# CPU_JTAG_Power_PLL.net
KiCad netlist of a schematic drawn in Altium Designer
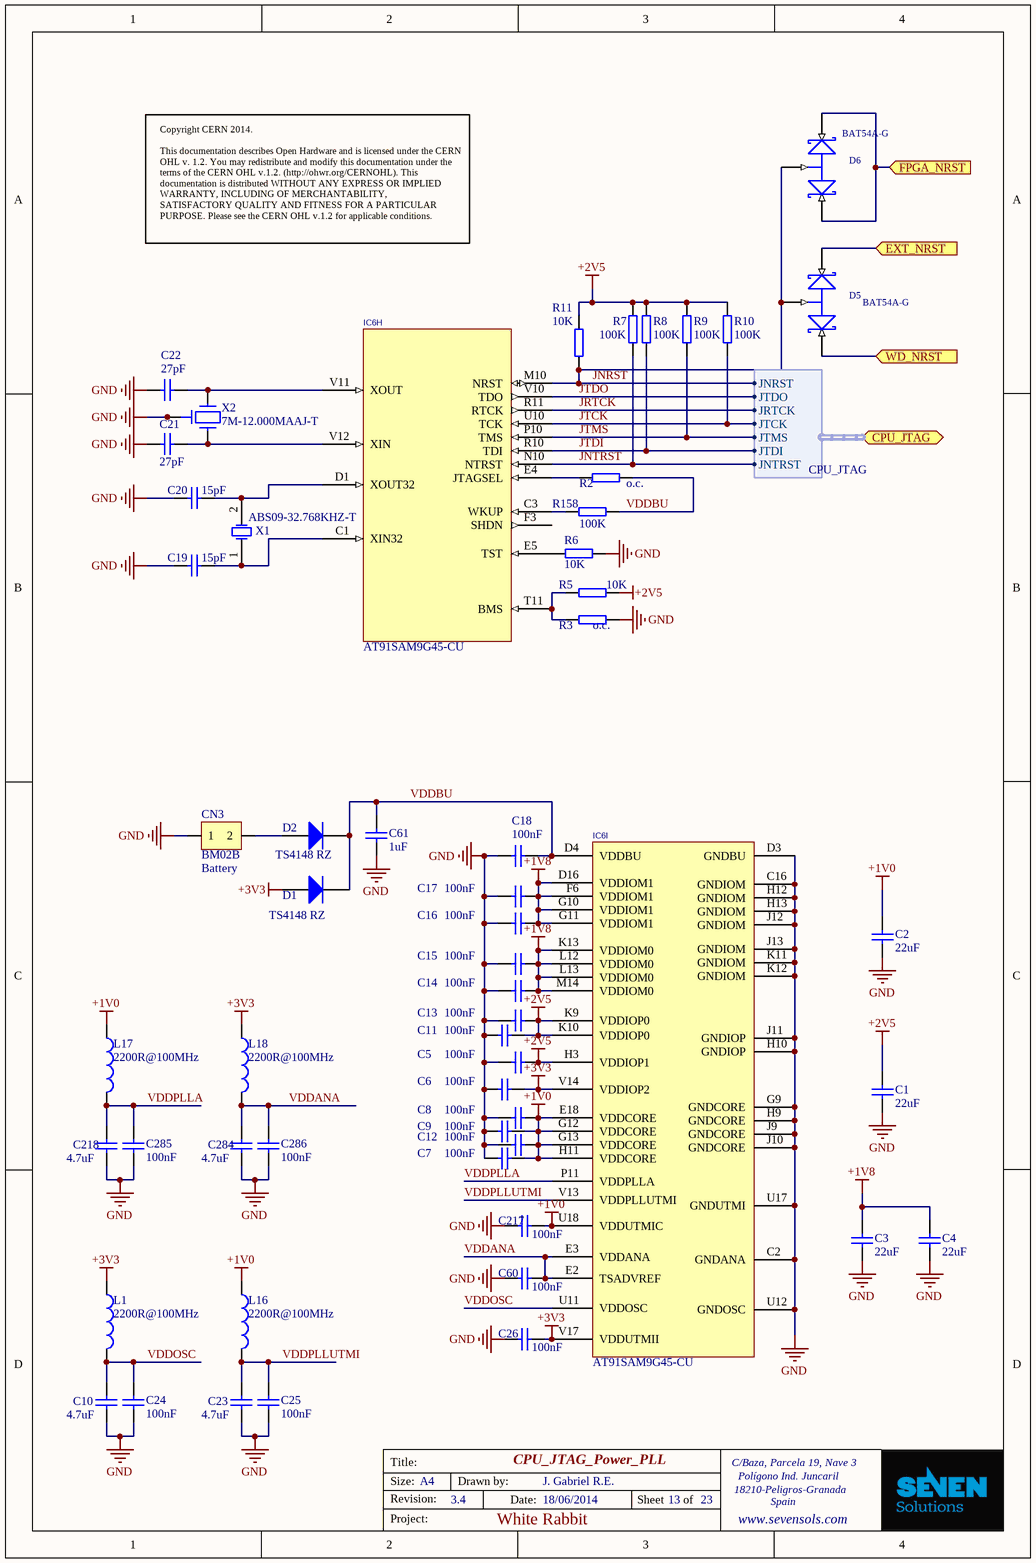
[diagram p0: CPU_JTAG_Power_PLL.SchDoc]

(export (version "E")
  (design (tool "Eeschema 10.0.6"))
  (components
    (comp (ref "C1")
      (value "22uF")
      (footprint "CC2012-0805")
      (description "Capacitor")
      (fields
        (field (name "TOLERANCE") "±20%")
        (field (name "VOLTAGE") "6.3V")
        (field (name "PUBLISHER") "Altium Limited")
      )
      (libsource (lib "wr_switch") (part "Cap"))
    )
    (comp (ref "C2")
      (value "22uF")
      (footprint "CC2012-0805")
      (description "Capacitor")
      (fields
        (field (name "TOLERANCE") "±20%")
        (field (name "VOLTAGE") "6.3V")
        (field (name "PUBLISHER") "Altium Limited")
      )
      (libsource (lib "wr_switch") (part "Cap"))
    )
    (comp (ref "C3")
      (value "22uF")
      (footprint "CC2012-0805")
      (description "Capacitor")
      (fields
        (field (name "TOLERANCE") "±20%")
        (field (name "VOLTAGE") "6.3V")
        (field (name "PUBLISHER") "Altium Limited")
      )
      (libsource (lib "wr_switch") (part "Cap"))
    )
    (comp (ref "C4")
      (value "22uF")
      (footprint "CC2012-0805")
      (description "Capacitor")
      (fields
        (field (name "TOLERANCE") "±20%")
        (field (name "VOLTAGE") "6.3V")
        (field (name "PUBLISHER") "Altium Limited")
      )
      (libsource (lib "wr_switch") (part "Cap"))
    )
    (comp (ref "C5")
      (value "100nF")
      (footprint "CC1005-0402")
      (description "Capacitor")
      (fields
        (field (name "TOLERANCE") "±10%")
        (field (name "VOLTAGE") "16V")
        (field (name "PUBLISHER") "Altium Limited")
      )
      (libsource (lib "wr_switch") (part "Cap"))
    )
    (comp (ref "C6")
      (value "100nF")
      (footprint "CC1005-0402")
      (description "Capacitor")
      (fields
        (field (name "TOLERANCE") "±10%")
        (field (name "VOLTAGE") "16V")
        (field (name "PUBLISHER") "Altium Limited")
      )
      (libsource (lib "wr_switch") (part "Cap"))
    )
    (comp (ref "C7")
      (value "100nF")
      (footprint "CC1005-0402")
      (description "Capacitor")
      (fields
        (field (name "TOLERANCE") "±10%")
        (field (name "VOLTAGE") "16V")
        (field (name "PUBLISHER") "Altium Limited")
      )
      (libsource (lib "wr_switch") (part "Cap"))
    )
    (comp (ref "C8")
      (value "100nF")
      (footprint "CC1005-0402")
      (description "Capacitor")
      (fields
        (field (name "TOLERANCE") "±10%")
        (field (name "VOLTAGE") "16V")
        (field (name "PUBLISHER") "Altium Limited")
      )
      (libsource (lib "wr_switch") (part "Cap"))
    )
    (comp (ref "C9")
      (value "100nF")
      (footprint "CC1005-0402")
      (description "Capacitor")
      (fields
        (field (name "TOLERANCE") "±10%")
        (field (name "VOLTAGE") "16V")
        (field (name "PUBLISHER") "Altium Limited")
      )
      (libsource (lib "wr_switch") (part "Cap"))
    )
    (comp (ref "C10")
      (value "4.7uF")
      (footprint "CC1608-0603")
      (description "Capacitor")
      (fields
        (field (name "TOLERANCE") "±10%")
        (field (name "VOLTAGE") "10V")
        (field (name "PUBLISHER") "Altium Limited")
      )
      (libsource (lib "wr_switch") (part "Cap"))
    )
    (comp (ref "C11")
      (value "100nF")
      (footprint "CC1005-0402")
      (description "Capacitor")
      (fields
        (field (name "TOLERANCE") "±10%")
        (field (name "VOLTAGE") "16V")
        (field (name "PUBLISHER") "Altium Limited")
      )
      (libsource (lib "wr_switch") (part "Cap"))
    )
    (comp (ref "C12")
      (value "100nF")
      (footprint "CC1005-0402")
      (description "Capacitor")
      (fields
        (field (name "TOLERANCE") "±10%")
        (field (name "VOLTAGE") "16V")
        (field (name "PUBLISHER") "Altium Limited")
      )
      (libsource (lib "wr_switch") (part "Cap"))
    )
    (comp (ref "C13")
      (value "100nF")
      (footprint "CC1005-0402")
      (description "Capacitor")
      (fields
        (field (name "TOLERANCE") "±10%")
        (field (name "VOLTAGE") "16V")
        (field (name "PUBLISHER") "Altium Limited")
      )
      (libsource (lib "wr_switch") (part "Cap"))
    )
    (comp (ref "C14")
      (value "100nF")
      (footprint "CC1005-0402")
      (description "Capacitor")
      (fields
        (field (name "TOLERANCE") "±10%")
        (field (name "VOLTAGE") "16V")
        (field (name "PUBLISHER") "Altium Limited")
      )
      (libsource (lib "wr_switch") (part "Cap"))
    )
    (comp (ref "C15")
      (value "100nF")
      (footprint "CC1005-0402")
      (description "Capacitor")
      (fields
        (field (name "TOLERANCE") "±10%")
        (field (name "VOLTAGE") "16V")
        (field (name "PUBLISHER") "Altium Limited")
      )
      (libsource (lib "wr_switch") (part "Cap"))
    )
    (comp (ref "C16")
      (value "100nF")
      (footprint "CC1005-0402")
      (description "Capacitor")
      (fields
        (field (name "TOLERANCE") "±10%")
        (field (name "VOLTAGE") "16V")
        (field (name "PUBLISHER") "Altium Limited")
      )
      (libsource (lib "wr_switch") (part "Cap"))
    )
    (comp (ref "C17")
      (value "100nF")
      (footprint "CC1005-0402")
      (description "Capacitor")
      (fields
        (field (name "TOLERANCE") "±10%")
        (field (name "VOLTAGE") "16V")
        (field (name "PUBLISHER") "Altium Limited")
      )
      (libsource (lib "wr_switch") (part "Cap"))
    )
    (comp (ref "C18")
      (value "100nF")
      (footprint "CC1005-0402")
      (description "Capacitor")
      (fields
        (field (name "TOLERANCE") "±10%")
        (field (name "VOLTAGE") "16V")
        (field (name "PUBLISHER") "Altium Limited")
      )
      (libsource (lib "wr_switch") (part "Cap"))
    )
    (comp (ref "C19")
      (value "15pF")
      (footprint "CC1005-0402")
      (description "Capacitor")
      (fields
        (field (name "TOLERANCE") "±5%")
        (field (name "VOLTAGE") "50V")
        (field (name "PUBLISHER") "Altium Limited")
      )
      (libsource (lib "wr_switch") (part "Cap"))
    )
    (comp (ref "C20")
      (value "15pF")
      (footprint "CC1005-0402")
      (description "Capacitor")
      (fields
        (field (name "TOLERANCE") "±5%")
        (field (name "VOLTAGE") "50V")
        (field (name "PUBLISHER") "Altium Limited")
      )
      (libsource (lib "wr_switch") (part "Cap"))
    )
    (comp (ref "C21")
      (value "27pF")
      (footprint "CC1005-0402")
      (description "Capacitor")
      (fields
        (field (name "TOLERANCE") "±5%")
        (field (name "VOLTAGE") "50V")
        (field (name "PUBLISHER") "Altium Limited")
      )
      (libsource (lib "wr_switch") (part "Cap"))
    )
    (comp (ref "C22")
      (value "27pF")
      (footprint "CC1005-0402")
      (description "Capacitor")
      (fields
        (field (name "TOLERANCE") "±5%")
        (field (name "VOLTAGE") "50V")
        (field (name "PUBLISHER") "Altium Limited")
      )
      (libsource (lib "wr_switch") (part "Cap"))
    )
    (comp (ref "C23")
      (value "4.7uF")
      (footprint "CC1608-0603")
      (description "Capacitor")
      (fields
        (field (name "TOLERANCE") "±10%")
        (field (name "VOLTAGE") "10V")
        (field (name "PUBLISHER") "Altium Limited")
      )
      (libsource (lib "wr_switch") (part "Cap"))
    )
    (comp (ref "C24")
      (value "100nF")
      (footprint "CC1005-0402")
      (description "Capacitor")
      (fields
        (field (name "TOLERANCE") "±10%")
        (field (name "VOLTAGE") "16V")
        (field (name "PUBLISHER") "Altium Limited")
      )
      (libsource (lib "wr_switch") (part "Cap"))
    )
    (comp (ref "C25")
      (value "100nF")
      (footprint "CC1005-0402")
      (description "Capacitor")
      (fields
        (field (name "TOLERANCE") "±10%")
        (field (name "VOLTAGE") "16V")
        (field (name "PUBLISHER") "Altium Limited")
      )
      (libsource (lib "wr_switch") (part "Cap"))
    )
    (comp (ref "C26")
      (value "100nF")
      (footprint "CC1005-0402")
      (description "Capacitor")
      (fields
        (field (name "TOLERANCE") "±10%")
        (field (name "VOLTAGE") "16V")
        (field (name "PUBLISHER") "Altium Limited")
      )
      (libsource (lib "wr_switch") (part "Cap"))
    )
    (comp (ref "C60")
      (value "100nF")
      (footprint "CC1005-0402")
      (description "Capacitor")
      (fields
        (field (name "TOLERANCE") "±10%")
        (field (name "VOLTAGE") "16V")
        (field (name "PUBLISHER") "Altium Limited")
      )
      (libsource (lib "wr_switch") (part "Cap"))
    )
    (comp (ref "C61")
      (value "1uF")
      (footprint "CC1005-0402")
      (description "Capacitor")
      (fields
        (field (name "TOLERANCE") "±10%")
        (field (name "VOLTAGE") "16V")
        (field (name "PUBLISHER") "Altium Limited")
      )
      (libsource (lib "wr_switch") (part "Cap"))
    )
    (comp (ref "C217")
      (value "100nF")
      (footprint "CC1005-0402")
      (description "Capacitor")
      (fields
        (field (name "TOLERANCE") "±10%")
        (field (name "VOLTAGE") "16V")
        (field (name "PUBLISHER") "Altium Limited")
      )
      (libsource (lib "wr_switch") (part "Cap"))
    )
    (comp (ref "C218")
      (value "4.7uF")
      (footprint "CC1608-0603")
      (description "Capacitor")
      (fields
        (field (name "TOLERANCE") "±10%")
        (field (name "VOLTAGE") "10V")
        (field (name "PUBLISHER") "Altium Limited")
      )
      (libsource (lib "wr_switch") (part "Cap"))
    )
    (comp (ref "C284")
      (value "4.7uF")
      (footprint "CC1608-0603")
      (description "Capacitor")
      (fields
        (field (name "TOLERANCE") "±10%")
        (field (name "VOLTAGE") "10V")
        (field (name "PUBLISHER") "Altium Limited")
      )
      (libsource (lib "wr_switch") (part "Cap"))
    )
    (comp (ref "C285")
      (value "100nF")
      (footprint "CC1005-0402")
      (description "Capacitor")
      (fields
        (field (name "TOLERANCE") "±10%")
        (field (name "VOLTAGE") "16V")
        (field (name "PUBLISHER") "Altium Limited")
      )
      (libsource (lib "wr_switch") (part "Cap"))
    )
    (comp (ref "C286")
      (value "100nF")
      (footprint "CC1005-0402")
      (description "Capacitor")
      (fields
        (field (name "TOLERANCE") "±10%")
        (field (name "VOLTAGE") "16V")
        (field (name "PUBLISHER") "Altium Limited")
      )
      (libsource (lib "wr_switch") (part "Cap"))
    )
    (comp (ref "CN3")
      (value "BM02B")
      (footprint "SH_CRIMP_1MM_2")
      (fields (field (name "COMMENT2") "Battery"))
      (libsource (lib "wr_switch") (part "CON_SH_CRIMP_1MM_2"))
    )
    (comp (ref "D1")
      (value "TS4148 RZ")
      (footprint "CD1608-0603")
      (description "Default Diode")
      (fields (field (name "PUBLISHER") "Altium Limited"))
      (libsource (lib "Miscellaneous Devices") (part "Diode"))
    )
    (comp (ref "D2")
      (value "TS4148 RZ")
      (footprint "CD1608-0603")
      (description "Default Diode")
      (fields (field (name "PUBLISHER") "Altium Limited"))
      (libsource (lib "Miscellaneous Devices") (part "Diode"))
    )
    (comp (ref "D5")
      (value "BAT54A-G")
      (footprint "SOT23")
      (description "Schottky Barrier Double Diode")
      (fields (field (name "PUBLISHER") "Altium Limited"))
      (libsource (lib "wr_switch") (part "BAT54A.1"))
    )
    (comp (ref "D6")
      (value "BAT54A-G")
      (footprint "SOT23")
      (description "Schottky Barrier Double Diode")
      (fields (field (name "PUBLISHER") "Altium Limited"))
      (libsource (lib "wr_switch") (part "BAT54A.1"))
    )
    (comp (ref "IC6")
      (value "AT91SAM9G45-CU")
      (footprint "TFBGA324")
      (description "Atmel 400MHz ARM926 MCU")
      (libsource (lib "wr_switch") (part "AT91SAM9G45-CU"))
    )
    (comp (ref "L1")
      (value "2200R@100MHz Ferrite Bead")
      (footprint "0805")
      (description "ferrite bead")
      (fields (field (name "IMPEDANCE") "2200R@100MHz"))
      (libsource (lib "wr_switch") (part "L_FERRITE_BEAD"))
    )
    (comp (ref "L16")
      (value "2200R@100MHz Ferrite Bead")
      (footprint "0805")
      (description "ferrite bead")
      (fields (field (name "IMPEDANCE") "2200R@100MHz"))
      (libsource (lib "wr_switch") (part "L_FERRITE_BEAD"))
    )
    (comp (ref "L17")
      (value "2200R@100MHz Ferrite Bead")
      (footprint "0805")
      (description "ferrite bead")
      (fields (field (name "IMPEDANCE") "2200R@100MHz"))
      (libsource (lib "wr_switch") (part "L_FERRITE_BEAD"))
    )
    (comp (ref "L18")
      (value "2200R@100MHz Ferrite Bead")
      (footprint "0805")
      (description "ferrite bead")
      (fields (field (name "IMPEDANCE") "2200R@100MHz"))
      (libsource (lib "wr_switch") (part "L_FERRITE_BEAD"))
    )
    (comp (ref "R2")
      (value "o.c.")
      (footprint "0402")
      (description "SMD Resistor")
      (libsource (lib "wr_switch") (part "RES_SMD"))
    )
    (comp (ref "R3")
      (value "o.c.")
      (footprint "0402")
      (description "SMD Resistor")
      (libsource (lib "wr_switch") (part "RES_SMD"))
    )
    (comp (ref "R5")
      (value "10K")
      (footprint "0402")
      (description "SMD Resistor")
      (fields (field (name "TOLERANCE") "±1%") (field (name "Comment") "10k"))
      (libsource (lib "wr_switch") (part "RES_SMD"))
    )
    (comp (ref "R6")
      (value "10K")
      (footprint "0402")
      (description "SMD Resistor")
      (fields (field (name "TOLERANCE") "±1%") (field (name "Comment") "10k"))
      (libsource (lib "wr_switch") (part "RES_SMD"))
    )
    (comp (ref "R7")
      (value "100K")
      (footprint "0402")
      (description "SMD Resistor")
      (fields (field (name "TOLERANCE") "±1%"))
      (libsource (lib "wr_switch") (part "RES_SMD"))
    )
    (comp (ref "R8")
      (value "100K")
      (footprint "0402")
      (description "SMD Resistor")
      (fields (field (name "TOLERANCE") "±1%"))
      (libsource (lib "wr_switch") (part "RES_SMD"))
    )
    (comp (ref "R9")
      (value "100K")
      (footprint "0402")
      (description "SMD Resistor")
      (fields (field (name "TOLERANCE") "±1%"))
      (libsource (lib "wr_switch") (part "RES_SMD"))
    )
    (comp (ref "R10")
      (value "100K")
      (footprint "0402")
      (description "SMD Resistor")
      (fields (field (name "TOLERANCE") "±1%"))
      (libsource (lib "wr_switch") (part "RES_SMD"))
    )
    (comp (ref "R11")
      (value "10K")
      (footprint "0402")
      (description "SMD Resistor")
      (fields (field (name "TOLERANCE") "±1%") (field (name "Comment") "10k"))
      (libsource (lib "wr_switch") (part "RES_SMD"))
    )
    (comp (ref "R158")
      (value "100K")
      (footprint "0402")
      (description "SMD Resistor")
      (fields (field (name "TOLERANCE") "±1%"))
      (libsource (lib "wr_switch") (part "RES_SMD"))
    )
    (comp (ref "X1")
      (value "ABS09-32.768KHZ-T")
      (footprint "XTAL_abs09")
      (description "Crystal Oscillator 12pF")
      (fields (field (name "MANUFACTURER") "Raltron") (field (name "PUBLISHER") "Altium Limited"))
      (libsource (lib "Miscellaneous Devices") (part "XTAL"))
    )
    (comp (ref "X2")
      (value "7M-12.000MAAJ-T")
      (footprint "OSC_IQD_CFPS-39")
      (description "SMD Crystal 7M Series 18pF 30 ppm")
      (libsource (lib "wr_switch") (part "X_CRYSTAL_SMD_7M"))
    )
  )
  (nets
    (net (code "2") (name "+1V0") (class "Default")
      (node (ref "C12") (pin "1") (pinfunction "1_1") (pintype "passive"))
      (node (ref "C2") (pin "2") (pinfunction "2_2") (pintype "passive"))
      (node (ref "C217") (pin "2") (pinfunction "2_2") (pintype "passive"))
      (node (ref "C7") (pin "1") (pinfunction "1_1") (pintype "passive"))
      (node (ref "C8") (pin "1") (pinfunction "1_1") (pintype "passive"))
      (node (ref "C9") (pin "1") (pinfunction "1_1") (pintype "passive"))
      (node (ref "IC6") (pin "E18") (pinfunction "VDDCORE_E18") (pintype "power_in"))
      (node (ref "IC6") (pin "G12") (pinfunction "VDDCORE_G12") (pintype "power_in"))
      (node (ref "IC6") (pin "G13") (pinfunction "VDDCORE_G13") (pintype "power_in"))
      (node (ref "IC6") (pin "H11") (pinfunction "VDDCORE_H11") (pintype "power_in"))
      (node (ref "IC6") (pin "U18") (pinfunction "VDDUTMIC_U18") (pintype "power_in"))
      (node (ref "L16") (pin "1") (pinfunction "1_1") (pintype "passive"))
      (node (ref "L17") (pin "1") (pinfunction "1_1") (pintype "passive"))
    )
    (net (code "3") (name "+1V8") (class "Default")
      (node (ref "C14") (pin "1") (pinfunction "1_1") (pintype "passive"))
      (node (ref "C15") (pin "1") (pinfunction "1_1") (pintype "passive"))
      (node (ref "C16") (pin "1") (pinfunction "1_1") (pintype "passive"))
      (node (ref "C17") (pin "1") (pinfunction "1_1") (pintype "passive"))
      (node (ref "C3") (pin "2") (pinfunction "2_2") (pintype "passive"))
      (node (ref "C4") (pin "2") (pinfunction "2_2") (pintype "passive"))
      (node (ref "IC6") (pin "D16") (pinfunction "VDDIOM1_D16") (pintype "power_in"))
      (node (ref "IC6") (pin "F6") (pinfunction "VDDIOM1_F6") (pintype "power_in"))
      (node (ref "IC6") (pin "G10") (pinfunction "VDDIOM1_G10") (pintype "power_in"))
      (node (ref "IC6") (pin "G11") (pinfunction "VDDIOM1_G11") (pintype "power_in"))
      (node (ref "IC6") (pin "K13") (pinfunction "VDDIOM0_K13") (pintype "power_in"))
      (node (ref "IC6") (pin "L12") (pinfunction "VDDIOM0_L12") (pintype "power_in"))
      (node (ref "IC6") (pin "L13") (pinfunction "VDDIOM0_L13") (pintype "power_in"))
      (node (ref "IC6") (pin "M14") (pinfunction "VDDIOM0_M14") (pintype "power_in"))
    )
    (net (code "4") (name "+2V5") (class "Default")
      (node (ref "C1") (pin "2") (pinfunction "2_2") (pintype "passive"))
      (node (ref "C11") (pin "1") (pinfunction "1_1") (pintype "passive"))
      (node (ref "C13") (pin "1") (pinfunction "1_1") (pintype "passive"))
      (node (ref "C5") (pin "1") (pinfunction "1_1") (pintype "passive"))
      (node (ref "IC6") (pin "H3") (pinfunction "VDDIOP1_H3") (pintype "power_in"))
      (node (ref "IC6") (pin "K10") (pinfunction "VDDIOP0_K10") (pintype "power_in"))
      (node (ref "IC6") (pin "K9") (pinfunction "VDDIOP0_K9") (pintype "power_in"))
      (node (ref "R10") (pin "2") (pinfunction "2_2") (pintype "passive"))
      (node (ref "R11") (pin "2") (pinfunction "2_2") (pintype "passive"))
      (node (ref "R5") (pin "1") (pinfunction "1_1") (pintype "passive"))
      (node (ref "R7") (pin "2") (pinfunction "2_2") (pintype "passive"))
      (node (ref "R8") (pin "2") (pinfunction "2_2") (pintype "passive"))
      (node (ref "R9") (pin "2") (pinfunction "2_2") (pintype "passive"))
    )
    (net (code "5") (name "+3V3") (class "Default")
      (node (ref "C26") (pin "2") (pinfunction "2_2") (pintype "passive"))
      (node (ref "C6") (pin "1") (pinfunction "1_1") (pintype "passive"))
      (node (ref "D1") (pin "1") (pinfunction "A_1") (pintype "passive"))
      (node (ref "IC6") (pin "V14") (pinfunction "VDDIOP2_V14") (pintype "power_in"))
      (node (ref "IC6") (pin "V17") (pinfunction "VDDUTMII_V17") (pintype "power_in"))
      (node (ref "L1") (pin "1") (pinfunction "1_1") (pintype "passive"))
      (node (ref "L18") (pin "1") (pinfunction "1_1") (pintype "passive"))
    )
    (net (code "6") (name "/EXT_NRST") (class "Default")
      (node (ref "D5") (pin "2") (pinfunction "K2_2") (pintype "input"))
    )
    (net (code "7") (name "/FPGA_NRST") (class "Default")
      (node (ref "D6") (pin "1") (pinfunction "K1_1") (pintype "input"))
      (node (ref "D6") (pin "2") (pinfunction "K2_2") (pintype "input"))
    )
    (net (code "8") (name "/JNRST") (class "Default")
      (node (ref "D5") (pin "3") (pinfunction "A_3") (pintype "input"))
      (node (ref "D6") (pin "3") (pinfunction "A_3") (pintype "input"))
      (node (ref "IC6") (pin "M10") (pinfunction "NRST_M10") (pintype "bidirectional"))
      (node (ref "R11") (pin "1") (pinfunction "1_1") (pintype "passive"))
    )
    (net (code "9") (name "/JNTRST") (class "Default")
      (node (ref "IC6") (pin "N10") (pinfunction "NTRST_N10") (pintype "input"))
      (node (ref "R7") (pin "1") (pinfunction "1_1") (pintype "passive"))
    )
    (net (code "10") (name "/JRTCK") (class "Default")
      (node (ref "IC6") (pin "R11") (pinfunction "RTCK_R11") (pintype "output"))
    )
    (net (code "11") (name "/JTCK") (class "Default")
      (node (ref "IC6") (pin "U10") (pinfunction "TCK_U10") (pintype "input"))
      (node (ref "R10") (pin "1") (pinfunction "1_1") (pintype "passive"))
    )
    (net (code "12") (name "/JTDI") (class "Default")
      (node (ref "IC6") (pin "R10") (pinfunction "TDI_R10") (pintype "input"))
      (node (ref "R8") (pin "1") (pinfunction "1_1") (pintype "passive"))
    )
    (net (code "13") (name "/JTDO") (class "Default")
      (node (ref "IC6") (pin "V10") (pinfunction "TDO_V10") (pintype "output"))
    )
    (net (code "14") (name "/JTMS") (class "Default")
      (node (ref "IC6") (pin "P10") (pinfunction "TMS_P10") (pintype "input"))
      (node (ref "R9") (pin "1") (pinfunction "1_1") (pintype "passive"))
    )
    (net (code "15") (name "/VDDANA") (class "Default")
      (node (ref "C284") (pin "2") (pinfunction "2_2") (pintype "passive"))
      (node (ref "C286") (pin "1") (pinfunction "1_1") (pintype "passive"))
      (node (ref "C60") (pin "2") (pinfunction "2_2") (pintype "passive"))
      (node (ref "IC6") (pin "E2") (pinfunction "TSADVREF_E2") (pintype "power_in"))
      (node (ref "IC6") (pin "E3") (pinfunction "VDDANA_E3") (pintype "power_in"))
      (node (ref "L18") (pin "2") (pinfunction "2_2") (pintype "passive"))
    )
    (net (code "16") (name "/VDDBU") (class "Default")
      (node (ref "C18") (pin "1") (pinfunction "1_1") (pintype "passive"))
      (node (ref "C61") (pin "2") (pinfunction "2_2") (pintype "passive"))
      (node (ref "D1") (pin "2") (pinfunction "K_2") (pintype "passive"))
      (node (ref "D2") (pin "2") (pinfunction "K_2") (pintype "passive"))
      (node (ref "IC6") (pin "D4") (pinfunction "VDDBU_D4") (pintype "power_in"))
      (node (ref "R158") (pin "2") (pinfunction "2_2") (pintype "passive"))
      (node (ref "R2") (pin "2") (pinfunction "2_2") (pintype "passive"))
    )
    (net (code "17") (name "/VDDOSC") (class "Default")
      (node (ref "C10") (pin "2") (pinfunction "2_2") (pintype "passive"))
      (node (ref "C24") (pin "1") (pinfunction "1_1") (pintype "passive"))
      (node (ref "IC6") (pin "U11") (pinfunction "VDDOSC_U11") (pintype "power_in"))
      (node (ref "L1") (pin "2") (pinfunction "2_2") (pintype "passive"))
    )
    (net (code "18") (name "/VDDPLLA") (class "Default")
      (node (ref "C218") (pin "2") (pinfunction "2_2") (pintype "passive"))
      (node (ref "C285") (pin "1") (pinfunction "1_1") (pintype "passive"))
      (node (ref "IC6") (pin "P11") (pinfunction "VDDPLLA_P11") (pintype "power_in"))
      (node (ref "L17") (pin "2") (pinfunction "2_2") (pintype "passive"))
    )
    (net (code "19") (name "/VDDPLLUTMI") (class "Default")
      (node (ref "C23") (pin "2") (pinfunction "2_2") (pintype "passive"))
      (node (ref "C25") (pin "1") (pinfunction "1_1") (pintype "passive"))
      (node (ref "IC6") (pin "V13") (pinfunction "VDDPLLUTMI_V13") (pintype "power_in"))
      (node (ref "L16") (pin "2") (pinfunction "2_2") (pintype "passive"))
    )
    (net (code "20") (name "/WD_NRST") (class "Default")
      (node (ref "D5") (pin "1") (pinfunction "K1_1") (pintype "input"))
    )
    (net (code "22") (name "GND") (class "Default")
      (node (ref "C1") (pin "1") (pinfunction "1_1") (pintype "passive"))
      (node (ref "C10") (pin "1") (pinfunction "1_1") (pintype "passive"))
      (node (ref "C11") (pin "2") (pinfunction "2_2") (pintype "passive"))
      (node (ref "C12") (pin "2") (pinfunction "2_2") (pintype "passive"))
      (node (ref "C13") (pin "2") (pinfunction "2_2") (pintype "passive"))
      (node (ref "C14") (pin "2") (pinfunction "2_2") (pintype "passive"))
      (node (ref "C15") (pin "2") (pinfunction "2_2") (pintype "passive"))
      (node (ref "C16") (pin "2") (pinfunction "2_2") (pintype "passive"))
      (node (ref "C17") (pin "2") (pinfunction "2_2") (pintype "passive"))
      (node (ref "C18") (pin "2") (pinfunction "2_2") (pintype "passive"))
      (node (ref "C19") (pin "1") (pinfunction "1_1") (pintype "passive"))
      (node (ref "C2") (pin "1") (pinfunction "1_1") (pintype "passive"))
      (node (ref "C20") (pin "1") (pinfunction "1_1") (pintype "passive"))
      (node (ref "C21") (pin "1") (pinfunction "1_1") (pintype "passive"))
      (node (ref "C217") (pin "1") (pinfunction "1_1") (pintype "passive"))
      (node (ref "C218") (pin "1") (pinfunction "1_1") (pintype "passive"))
      (node (ref "C22") (pin "1") (pinfunction "1_1") (pintype "passive"))
      (node (ref "C23") (pin "1") (pinfunction "1_1") (pintype "passive"))
      (node (ref "C24") (pin "2") (pinfunction "2_2") (pintype "passive"))
      (node (ref "C25") (pin "2") (pinfunction "2_2") (pintype "passive"))
      (node (ref "C26") (pin "1") (pinfunction "1_1") (pintype "passive"))
      (node (ref "C284") (pin "1") (pinfunction "1_1") (pintype "passive"))
      (node (ref "C285") (pin "2") (pinfunction "2_2") (pintype "passive"))
      (node (ref "C286") (pin "2") (pinfunction "2_2") (pintype "passive"))
      (node (ref "C3") (pin "1") (pinfunction "1_1") (pintype "passive"))
      (node (ref "C4") (pin "1") (pinfunction "1_1") (pintype "passive"))
      (node (ref "C5") (pin "2") (pinfunction "2_2") (pintype "passive"))
      (node (ref "C6") (pin "2") (pinfunction "2_2") (pintype "passive"))
      (node (ref "C60") (pin "1") (pinfunction "1_1") (pintype "passive"))
      (node (ref "C61") (pin "1") (pinfunction "1_1") (pintype "passive"))
      (node (ref "C7") (pin "2") (pinfunction "2_2") (pintype "passive"))
      (node (ref "C8") (pin "2") (pinfunction "2_2") (pintype "passive"))
      (node (ref "C9") (pin "2") (pinfunction "2_2") (pintype "passive"))
      (node (ref "CN3") (pin "1") (pinfunction "1_1") (pintype "passive"))
      (node (ref "IC6") (pin "C16") (pinfunction "GNDIOM_C16") (pintype "power_in"))
      (node (ref "IC6") (pin "C2") (pinfunction "GNDANA_C2") (pintype "power_in"))
      (node (ref "IC6") (pin "D3") (pinfunction "GNDBU_D3") (pintype "power_in"))
      (node (ref "IC6") (pin "G9") (pinfunction "GNDCORE_G9") (pintype "power_in"))
      (node (ref "IC6") (pin "H10") (pinfunction "GNDIOP_H10") (pintype "power_in"))
      (node (ref "IC6") (pin "H12") (pinfunction "GNDIOM_H12") (pintype "power_in"))
      (node (ref "IC6") (pin "H13") (pinfunction "GNDIOM_H13") (pintype "power_in"))
      (node (ref "IC6") (pin "H9") (pinfunction "GNDCORE_H9") (pintype "power_in"))
      (node (ref "IC6") (pin "J10") (pinfunction "GNDCORE_J10") (pintype "power_in"))
      (node (ref "IC6") (pin "J11") (pinfunction "GNDIOP_J11") (pintype "power_in"))
      (node (ref "IC6") (pin "J12") (pinfunction "GNDIOM_J12") (pintype "power_in"))
      (node (ref "IC6") (pin "J13") (pinfunction "GNDIOM_J13") (pintype "power_in"))
      (node (ref "IC6") (pin "J9") (pinfunction "GNDCORE_J9") (pintype "power_in"))
      (node (ref "IC6") (pin "K11") (pinfunction "GNDIOM_K11") (pintype "power_in"))
      (node (ref "IC6") (pin "K12") (pinfunction "GNDIOM_K12") (pintype "power_in"))
      (node (ref "IC6") (pin "U12") (pinfunction "GNDOSC_U12") (pintype "power_in"))
      (node (ref "IC6") (pin "U17") (pinfunction "GNDUTMI_U17") (pintype "power_in"))
      (node (ref "R3") (pin "2") (pinfunction "2_2") (pintype "passive"))
      (node (ref "R6") (pin "1") (pinfunction "1_1") (pintype "passive"))
      (node (ref "X2") (pin "2") (pinfunction "2_2") (pintype "passive"))
      (node (ref "X2") (pin "4") (pinfunction "4_4") (pintype "passive"))
    )
    (net (code "23") (name "Net-(D2-A)") (class "Default")
      (node (ref "CN3") (pin "2") (pinfunction "2_2") (pintype "passive"))
      (node (ref "D2") (pin "1") (pinfunction "A_1") (pintype "passive"))
    )
    (net (code "24") (name "Net-(IC6H-BMS)") (class "Default")
      (node (ref "IC6") (pin "T11") (pinfunction "BMS_T11") (pintype "input"))
      (node (ref "R3") (pin "1") (pinfunction "1_1") (pintype "passive"))
      (node (ref "R5") (pin "2") (pinfunction "2_2") (pintype "passive"))
    )
    (net (code "25") (name "Net-(IC6H-JTAGSEL)") (class "Default")
      (node (ref "IC6") (pin "E4") (pinfunction "JTAGSEL_E4") (pintype "input"))
      (node (ref "R2") (pin "1") (pinfunction "1_1") (pintype "passive"))
    )
    (net (code "26") (name "Net-(IC6H-TST)") (class "Default")
      (node (ref "IC6") (pin "E5") (pinfunction "TST_E5") (pintype "input"))
      (node (ref "R6") (pin "2") (pinfunction "2_2") (pintype "passive"))
    )
    (net (code "27") (name "Net-(IC6H-WKUP)") (class "Default")
      (node (ref "IC6") (pin "C3") (pinfunction "WKUP_C3") (pintype "input"))
      (node (ref "R158") (pin "1") (pinfunction "1_1") (pintype "passive"))
    )
    (net (code "28") (name "Net-(IC6H-XIN)") (class "Default")
      (node (ref "C21") (pin "2") (pinfunction "2_2") (pintype "passive"))
      (node (ref "IC6") (pin "V12") (pinfunction "XIN_V12") (pintype "input"))
      (node (ref "X2") (pin "3") (pinfunction "3_3") (pintype "passive"))
    )
    (net (code "29") (name "Net-(IC6H-XIN32)") (class "Default")
      (node (ref "C19") (pin "2") (pinfunction "2_2") (pintype "passive"))
      (node (ref "IC6") (pin "C1") (pinfunction "XIN32_C1") (pintype "input"))
      (node (ref "X1") (pin "1") (pinfunction "OSC1_1") (pintype "passive"))
    )
    (net (code "30") (name "Net-(IC6H-XOUT)") (class "Default")
      (node (ref "C22") (pin "2") (pinfunction "2_2") (pintype "passive"))
      (node (ref "IC6") (pin "V11") (pinfunction "XOUT_V11") (pintype "input"))
      (node (ref "X2") (pin "1") (pinfunction "1_1") (pintype "passive"))
    )
    (net (code "31") (name "Net-(IC6H-XOUT32)") (class "Default")
      (node (ref "C20") (pin "2") (pinfunction "2_2") (pintype "passive"))
      (node (ref "IC6") (pin "D1") (pinfunction "XOUT32_D1") (pintype "input"))
      (node (ref "X1") (pin "2") (pinfunction "OSC2_2") (pintype "passive"))
    )
    (net (code "32") (name "unconnected-(IC6H-SHDN-PadF3)") (class "Default")
      (node (ref "IC6") (pin "F3") (pinfunction "SHDN_F3") (pintype "output"))
    )
  )
)
